# LT3752-Main.net
KiCad netlist of a schematic drawn in Altium Designer
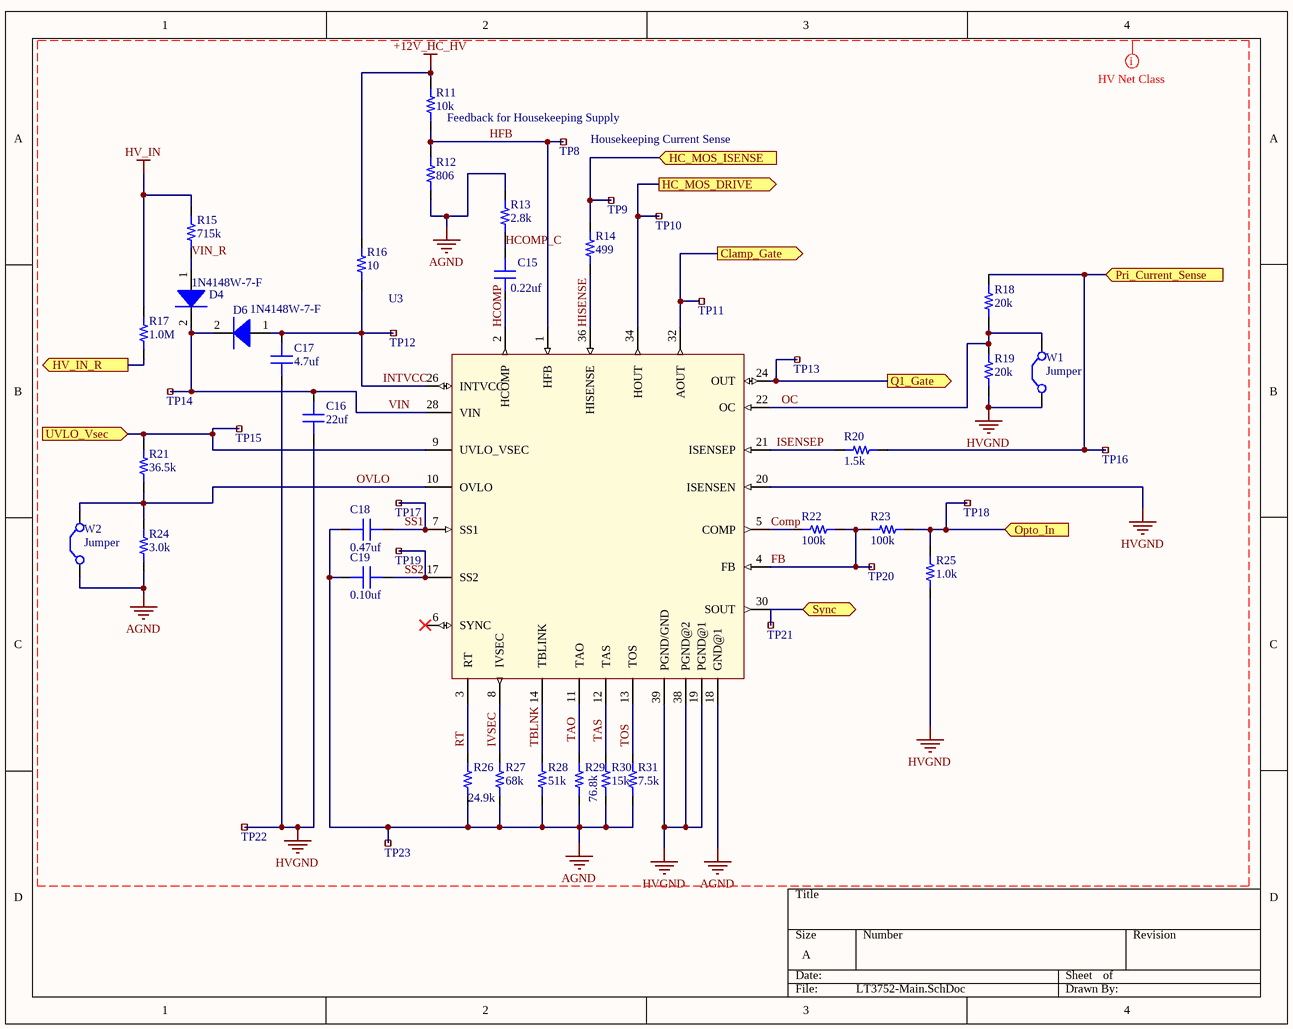
[diagram p0: LT3752-Main.SchDoc]

(export (version "E")
  (design (tool "Eeschema 10.0.6"))
  (components
    (comp (ref "C15")
      (value "0.22uf")
      (footprint "CAP 0603/1608")
      (fields
        (field (name "Comment") "Capacitor MLCC 0.22uf 25V CAP 0603/1608")
        (field (name "CREATED_BY") "Nick Mah")
      )
      (libsource (lib "Altium-Lib") (part "Capacitor"))
    )
    (comp (ref "C16")
      (value "22uf")
      (footprint "CAP 0805/2012")
      (fields
        (field (name "Comment") "Capacitor MLCC 22uf 25V CAP 0805/2012")
        (field (name "CREATED_BY") "Nick Mah")
      )
      (libsource (lib "Altium-Lib") (part "Capacitor"))
    )
    (comp (ref "C17")
      (value "4.7uf")
      (footprint "CAP 0805/2012")
      (fields
        (field (name "Comment") "Capacitor MLCC 4.7uf 25V CAP 0805/2012")
        (field (name "CREATED_BY") "Nick Mah")
      )
      (libsource (lib "Altium-Lib") (part "Capacitor"))
    )
    (comp (ref "C18")
      (value "0.47uf")
      (footprint "CAP 0603/1608")
      (fields
        (field (name "Comment") "Capacitor MLCC 0.47uf 25V CAP 0603/1608")
        (field (name "CREATED_BY") "Nick Mah")
      )
      (libsource (lib "Altium-Lib") (part "Capacitor"))
    )
    (comp (ref "C19")
      (value "0.10uf")
      (footprint "CAP 0603/1608")
      (fields
        (field (name "Comment") "Capacitor MLCC 0.10uf 25V CAP 0603/1608")
        (field (name "CREATED_BY") "Nick Mah")
      )
      (libsource (lib "Altium-Lib") (part "Capacitor"))
    )
    (comp (ref "D4")
      (value "~")
      (footprint "SOD123F")
      (description "100V Reverse DC Voltage")
      (fields (field (name "MFRPARTNO") "1N4148W-7-F"))
      (libsource (lib "Altium-Lib") (part "DIODE"))
    )
    (comp (ref "D6")
      (value "~")
      (footprint "SOD123F")
      (description "100V Reverse DC Voltage")
      (fields (field (name "MFRPARTNO") "1N4148W-7-F"))
      (libsource (lib "Altium-Lib") (part "DIODE"))
    )
    (comp (ref "R11")
      (value "10k")
      (footprint "RES 0603/1608")
      (fields
        (field (name "TOLERANCE") "1%")
        (field (name "POWER") "1/10W")
        (field (name "Comment") "Resistor 10k 0603 1/10W 1%")
        (field (name "CREATED_BY") "Nick Mah")
      )
      (libsource (lib "Altium-Lib") (part "Resistor"))
    )
    (comp (ref "R12")
      (value "806")
      (footprint "RES 0603/1608")
      (fields
        (field (name "TOLERANCE") "1%")
        (field (name "POWER") "1/10W")
        (field (name "Comment") "Resistor 806 0603 1/10W 1%")
        (field (name "CREATED_BY") "Nick Mah")
      )
      (libsource (lib "Altium-Lib") (part "Resistor"))
    )
    (comp (ref "R13")
      (value "2.8k")
      (footprint "RES 0603/1608")
      (fields
        (field (name "TOLERANCE") "1%")
        (field (name "POWER") "1/10W")
        (field (name "Comment") "Resistor 2.8k 0603 1/10W 1%")
        (field (name "CREATED_BY") "Nick Mah")
      )
      (libsource (lib "Altium-Lib") (part "Resistor"))
    )
    (comp (ref "R14")
      (value "499")
      (footprint "RES 0603/1608")
      (fields
        (field (name "TOLERANCE") "1%")
        (field (name "POWER") "1/10W")
        (field (name "Comment") "Resistor 499 0603 1/10W 1%")
        (field (name "CREATED_BY") "Nick Mah")
      )
      (libsource (lib "Altium-Lib") (part "Resistor"))
    )
    (comp (ref "R15")
      (value "715k")
      (footprint "RES 1206/3216")
      (fields
        (field (name "TOLERANCE") "1%")
        (field (name "POWER") "1/4W")
        (field (name "Comment") "Resistor 715k 1206 1/4W 1%")
        (field (name "CREATED_BY") "Nick Mah")
      )
      (libsource (lib "Altium-Lib") (part "Resistor"))
    )
    (comp (ref "R16")
      (value "10")
      (footprint "RES 0805/2012")
      (fields
        (field (name "TOLERANCE") "10%")
        (field (name "POWER") "1/4W")
        (field (name "Comment") "Resistor 10 0805 1/4W 10%")
        (field (name "CREATED_BY") "Nick Mah")
      )
      (libsource (lib "Altium-Lib") (part "Resistor"))
    )
    (comp (ref "R17")
      (value "1.0M")
      (footprint "RES 0603/1608")
      (fields
        (field (name "TOLERANCE") "1%")
        (field (name "POWER") "1/10W")
        (field (name "Comment") "Resistor 1.0M 0603 1/10W 1%")
        (field (name "CREATED_BY") "Nick Mah")
      )
      (libsource (lib "Altium-Lib") (part "Resistor"))
    )
    (comp (ref "R18")
      (value "20k")
      (footprint "RES 0603/1608")
      (fields
        (field (name "TOLERANCE") "1%")
        (field (name "POWER") "1/10W")
        (field (name "Comment") "Resistor 20k 0603 1/10W 1%")
        (field (name "CREATED_BY") "Nick Mah")
      )
      (libsource (lib "Altium-Lib") (part "Resistor"))
    )
    (comp (ref "R19")
      (value "20k")
      (footprint "RES 0603/1608")
      (fields
        (field (name "TOLERANCE") "1%")
        (field (name "POWER") "1/10W")
        (field (name "Comment") "Resistor 20k 0603 1/10W 1%")
        (field (name "CREATED_BY") "Nick Mah")
      )
      (libsource (lib "Altium-Lib") (part "Resistor"))
    )
    (comp (ref "R20")
      (value "1.5k")
      (footprint "RES 0603/1608")
      (fields
        (field (name "TOLERANCE") "1%")
        (field (name "POWER") "1/10W")
        (field (name "Comment") "Resistor 1.5k 0603 1/10W 1%")
        (field (name "CREATED_BY") "Nick Mah")
      )
      (libsource (lib "Altium-Lib") (part "Resistor"))
    )
    (comp (ref "R21")
      (value "36.5k")
      (footprint "RES 0603/1608")
      (fields
        (field (name "TOLERANCE") "1%")
        (field (name "POWER") "1/10W")
        (field (name "Comment") "Resistor 36.5k 0603 1/10W 1%")
        (field (name "CREATED_BY") "Nick Mah")
      )
      (libsource (lib "Altium-Lib") (part "Resistor"))
    )
    (comp (ref "R22")
      (value "100k")
      (footprint "RES 0603/1608")
      (fields
        (field (name "TOLERANCE") "1%")
        (field (name "POWER") "1/10W")
        (field (name "Comment") "Resistor 100k 0603 1/10W 1%")
        (field (name "CREATED_BY") "Nick Mah")
      )
      (libsource (lib "Altium-Lib") (part "Resistor"))
    )
    (comp (ref "R23")
      (value "100k")
      (footprint "RES 0603/1608")
      (fields
        (field (name "TOLERANCE") "1%")
        (field (name "POWER") "1/10W")
        (field (name "Comment") "Resistor 100k 0603 1/10W 1%")
        (field (name "CREATED_BY") "Nick Mah")
      )
      (libsource (lib "Altium-Lib") (part "Resistor"))
    )
    (comp (ref "R24")
      (value "3.0k")
      (footprint "RES 0603/1608")
      (fields
        (field (name "TOLERANCE") "1%")
        (field (name "POWER") "1/10W")
        (field (name "Comment") "Resistor 3.0k 0603 1/10W 1%")
        (field (name "CREATED_BY") "Nick Mah")
      )
      (libsource (lib "Altium-Lib") (part "Resistor"))
    )
    (comp (ref "R25")
      (value "1.0k")
      (footprint "RES 0805/2012")
      (fields
        (field (name "TOLERANCE") "5%")
        (field (name "POWER") "1/4W")
        (field (name "Comment") "Resistor 1.0k 0805 1/4W 5%")
        (field (name "CREATED_BY") "Nick Mah")
      )
      (libsource (lib "Altium-Lib") (part "Resistor"))
    )
    (comp (ref "R26")
      (value "24.9k")
      (footprint "RES 0603/1608")
      (fields
        (field (name "TOLERANCE") "1%")
        (field (name "POWER") "1/10W")
        (field (name "Comment") "Resistor 24.9k 0603 1/10W 1%")
        (field (name "CREATED_BY") "Nick Mah")
      )
      (libsource (lib "Altium-Lib") (part "Resistor"))
    )
    (comp (ref "R27")
      (value "68k")
      (footprint "RES 0603/1608")
      (fields
        (field (name "TOLERANCE") "1%")
        (field (name "POWER") "1/10W")
        (field (name "Comment") "Resistor 68k 0603 1/10W 1%")
        (field (name "CREATED_BY") "Nick Mah")
      )
      (libsource (lib "Altium-Lib") (part "Resistor"))
    )
    (comp (ref "R28")
      (value "51k")
      (footprint "RES 0603/1608")
      (fields
        (field (name "TOLERANCE") "1%")
        (field (name "POWER") "1/10W")
        (field (name "Comment") "Resistor 51k 0603 1/10W 1%")
        (field (name "CREATED_BY") "Nick Mah")
      )
      (libsource (lib "Altium-Lib") (part "Resistor"))
    )
    (comp (ref "R29")
      (value "76.8k")
      (footprint "RES 0603/1608")
      (fields
        (field (name "TOLERANCE") "1%")
        (field (name "POWER") "1/10W")
        (field (name "Comment") "Resistor 76.8k 0603 1/10 1%")
        (field (name "CREATED_BY") "Nick Mah")
      )
      (libsource (lib "Altium-Lib") (part "Resistor"))
    )
    (comp (ref "R30")
      (value "15k")
      (footprint "RES 0603/1608")
      (fields
        (field (name "TOLERANCE") "1%")
        (field (name "POWER") "1/10W")
        (field (name "Comment") "Resistor 15k 0603 1/10W 1%")
        (field (name "CREATED_BY") "Nick Mah")
      )
      (libsource (lib "Altium-Lib") (part "Resistor"))
    )
    (comp (ref "R31")
      (value "7.5k")
      (footprint "RES 0603/1608")
      (fields
        (field (name "TOLERANCE") "1%")
        (field (name "POWER") "1/10W")
        (field (name "Comment") "Resistor 7.5k 0603 1/10W 1%")
        (field (name "CREATED_BY") "Nick Mah")
      )
      (libsource (lib "Altium-Lib") (part "Resistor"))
    )
    (comp (ref "TP8")
      (value "RCU-0C")
      (footprint "5029")
      (description "Test point")
      (fields
        (field (name "MFRPARTNO") "5029")
        (field (name "COMPONENTLINK1URL") "file:///C:/Users/Jason%20Zhou/Downloads/5029.PDF")
        (field (name "CREATED_BY") "Jason Zhou")
      )
      (libsource (lib "Altium-Lib") (part "RCU-0C"))
    )
    (comp (ref "TP9")
      (value "RCU-0C")
      (footprint "5029")
      (description "Test point")
      (fields
        (field (name "MFRPARTNO") "5029")
        (field (name "COMPONENTLINK1URL") "file:///C:/Users/Jason%20Zhou/Downloads/5029.PDF")
        (field (name "CREATED_BY") "Jason Zhou")
      )
      (libsource (lib "Altium-Lib") (part "RCU-0C"))
    )
    (comp (ref "TP10")
      (value "RCU-0C")
      (footprint "5029")
      (description "Test point")
      (fields
        (field (name "MFRPARTNO") "5029")
        (field (name "COMPONENTLINK1URL") "file:///C:/Users/Jason%20Zhou/Downloads/5029.PDF")
        (field (name "CREATED_BY") "Jason Zhou")
      )
      (libsource (lib "Altium-Lib") (part "RCU-0C"))
    )
    (comp (ref "TP11")
      (value "RCU-0C")
      (footprint "5029")
      (description "Test point")
      (fields
        (field (name "MFRPARTNO") "5029")
        (field (name "COMPONENTLINK1URL") "file:///C:/Users/Jason%20Zhou/Downloads/5029.PDF")
        (field (name "CREATED_BY") "Jason Zhou")
      )
      (libsource (lib "Altium-Lib") (part "RCU-0C"))
    )
    (comp (ref "TP12")
      (value "RCU-0C")
      (footprint "5029")
      (description "Test point")
      (fields
        (field (name "MFRPARTNO") "5029")
        (field (name "COMPONENTLINK1URL") "file:///C:/Users/Jason%20Zhou/Downloads/5029.PDF")
        (field (name "CREATED_BY") "Jason Zhou")
      )
      (libsource (lib "Altium-Lib") (part "RCU-0C"))
    )
    (comp (ref "TP13")
      (value "RCU-0C")
      (footprint "5029")
      (description "Test point")
      (fields
        (field (name "MFRPARTNO") "5029")
        (field (name "COMPONENTLINK1URL") "file:///C:/Users/Jason%20Zhou/Downloads/5029.PDF")
        (field (name "CREATED_BY") "Jason Zhou")
      )
      (libsource (lib "Altium-Lib") (part "RCU-0C"))
    )
    (comp (ref "TP14")
      (value "RCU-0C")
      (footprint "5029")
      (description "Test point")
      (fields
        (field (name "MFRPARTNO") "5029")
        (field (name "COMPONENTLINK1URL") "file:///C:/Users/Jason%20Zhou/Downloads/5029.PDF")
        (field (name "CREATED_BY") "Jason Zhou")
      )
      (libsource (lib "Altium-Lib") (part "RCU-0C"))
    )
    (comp (ref "TP15")
      (value "RCU-0C")
      (footprint "5029")
      (description "Test point")
      (fields
        (field (name "MFRPARTNO") "5029")
        (field (name "COMPONENTLINK1URL") "file:///C:/Users/Jason%20Zhou/Downloads/5029.PDF")
        (field (name "CREATED_BY") "Jason Zhou")
      )
      (libsource (lib "Altium-Lib") (part "RCU-0C"))
    )
    (comp (ref "TP16")
      (value "RCU-0C")
      (footprint "5029")
      (description "Test point")
      (fields
        (field (name "MFRPARTNO") "5029")
        (field (name "COMPONENTLINK1URL") "file:///C:/Users/Jason%20Zhou/Downloads/5029.PDF")
        (field (name "CREATED_BY") "Jason Zhou")
      )
      (libsource (lib "Altium-Lib") (part "RCU-0C"))
    )
    (comp (ref "TP17")
      (value "RCU-0C")
      (footprint "5029")
      (description "Test point")
      (fields
        (field (name "MFRPARTNO") "5029")
        (field (name "COMPONENTLINK1URL") "file:///C:/Users/Jason%20Zhou/Downloads/5029.PDF")
        (field (name "CREATED_BY") "Jason Zhou")
      )
      (libsource (lib "Altium-Lib") (part "RCU-0C"))
    )
    (comp (ref "TP18")
      (value "RCU-0C")
      (footprint "5029")
      (description "Test point")
      (fields
        (field (name "MFRPARTNO") "5029")
        (field (name "COMPONENTLINK1URL") "file:///C:/Users/Jason%20Zhou/Downloads/5029.PDF")
        (field (name "CREATED_BY") "Jason Zhou")
      )
      (libsource (lib "Altium-Lib") (part "RCU-0C"))
    )
    (comp (ref "TP19")
      (value "RCU-0C")
      (footprint "5029")
      (description "Test point")
      (fields
        (field (name "MFRPARTNO") "5029")
        (field (name "COMPONENTLINK1URL") "file:///C:/Users/Jason%20Zhou/Downloads/5029.PDF")
        (field (name "CREATED_BY") "Jason Zhou")
      )
      (libsource (lib "Altium-Lib") (part "RCU-0C"))
    )
    (comp (ref "TP20")
      (value "RCU-0C")
      (footprint "5029")
      (description "Test point")
      (fields
        (field (name "MFRPARTNO") "5029")
        (field (name "COMPONENTLINK1URL") "file:///C:/Users/Jason%20Zhou/Downloads/5029.PDF")
        (field (name "CREATED_BY") "Jason Zhou")
      )
      (libsource (lib "Altium-Lib") (part "RCU-0C"))
    )
    (comp (ref "TP21")
      (value "RCU-0C")
      (footprint "5029")
      (description "Test point")
      (fields
        (field (name "MFRPARTNO") "5029")
        (field (name "COMPONENTLINK1URL") "file:///C:/Users/Jason%20Zhou/Downloads/5029.PDF")
        (field (name "CREATED_BY") "Jason Zhou")
      )
      (libsource (lib "Altium-Lib") (part "RCU-0C"))
    )
    (comp (ref "TP22")
      (value "RCU-0C")
      (footprint "5029")
      (description "Test point")
      (fields
        (field (name "MFRPARTNO") "5029")
        (field (name "COMPONENTLINK1URL") "file:///C:/Users/Jason%20Zhou/Downloads/5029.PDF")
        (field (name "CREATED_BY") "Jason Zhou")
      )
      (libsource (lib "Altium-Lib") (part "RCU-0C"))
    )
    (comp (ref "TP23")
      (value "RCU-0C")
      (footprint "5029")
      (description "Test point")
      (fields
        (field (name "MFRPARTNO") "5029")
        (field (name "COMPONENTLINK1URL") "file:///C:/Users/Jason%20Zhou/Downloads/5029.PDF")
        (field (name "CREATED_BY") "Jason Zhou")
      )
      (libsource (lib "Altium-Lib") (part "RCU-0C"))
    )
    (comp (ref "U3")
      (value "~")
      (footprint "TSSOP-38")
      (fields
        (field (name "MF") "Linear Technology/Analog")
        (field (name "MP") "LT3752EFE-1#PBF")
        (field (name "POWER") "400W")
        (field (name "CREATED_BY") "Jason")
      )
      (libsource (lib "Altium-Lib") (part "LT3752-1"))
    )
    (comp (ref "W1")
      (value "Jumper")
      (footprint "XG8T-0231")
      (description "Jumper headers")
      (fields (field (name "MFRPARTNO") "XG8T-0231"))
      (libsource (lib "Altium-Lib") (part "Jumper"))
    )
    (comp (ref "W2")
      (value "Jumper")
      (footprint "XG8T-0231")
      (description "Jumper headers")
      (fields (field (name "MFRPARTNO") "XG8T-0231"))
      (libsource (lib "Altium-Lib") (part "Jumper"))
    )
  )
  (nets
    (net (code "1") (name "+12V_HC_HV") (class "Default")
      (node (ref "R11") (pin "1") (pinfunction "1_1") (pintype "passive"))
      (node (ref "R16") (pin "1") (pinfunction "1_1") (pintype "passive"))
    )
    (net (code "2") (name "/Clamp_Gate") (class "Default")
      (node (ref "TP11") (pin "1") (pintype "passive"))
      (node (ref "U3") (pin "32") (pinfunction "AOUT_32") (pintype "output"))
    )
    (net (code "3") (name "/Comp") (class "Default")
      (node (ref "R22") (pin "1") (pinfunction "1_1") (pintype "passive"))
      (node (ref "U3") (pin "5") (pinfunction "COMP_5") (pintype "output"))
    )
    (net (code "4") (name "/FB") (class "Default")
      (node (ref "R22") (pin "2") (pinfunction "2_2") (pintype "passive"))
      (node (ref "R23") (pin "1") (pinfunction "1_1") (pintype "passive"))
      (node (ref "TP20") (pin "1") (pintype "passive"))
      (node (ref "U3") (pin "4") (pinfunction "FB_4") (pintype "input"))
    )
    (net (code "5") (name "/HCOMP") (class "Default")
      (node (ref "C15") (pin "1") (pinfunction "1_1") (pintype "passive"))
      (node (ref "U3") (pin "2") (pinfunction "HCOMP_2") (pintype "output"))
    )
    (net (code "6") (name "/HCOMP_C") (class "Default")
      (node (ref "C15") (pin "2") (pinfunction "2_2") (pintype "passive"))
      (node (ref "R13") (pin "1") (pinfunction "1_1") (pintype "passive"))
    )
    (net (code "7") (name "/HC_MOS_DRIVE") (class "Default")
      (node (ref "TP10") (pin "1") (pintype "passive"))
      (node (ref "U3") (pin "34") (pinfunction "HOUT_34") (pintype "output"))
    )
    (net (code "8") (name "/HC_MOS_ISENSE") (class "Default")
      (node (ref "R14") (pin "2") (pinfunction "2_2") (pintype "passive"))
      (node (ref "TP9") (pin "1") (pintype "passive"))
    )
    (net (code "9") (name "/HFB") (class "Default")
      (node (ref "R11") (pin "2") (pinfunction "2_2") (pintype "passive"))
      (node (ref "R12") (pin "2") (pinfunction "2_2") (pintype "passive"))
      (node (ref "TP8") (pin "1") (pintype "passive"))
      (node (ref "U3") (pin "1") (pinfunction "HFB_1") (pintype "input"))
    )
    (net (code "10") (name "/HISENSE") (class "Default")
      (node (ref "R14") (pin "1") (pinfunction "1_1") (pintype "passive"))
      (node (ref "U3") (pin "36") (pinfunction "HISENSE_36") (pintype "input"))
    )
    (net (code "11") (name "/HV_IN_R") (class "Default")
      (node (ref "R17") (pin "2") (pinfunction "2_2") (pintype "passive"))
    )
    (net (code "12") (name "/INTVCC") (class "Default")
      (node (ref "C17") (pin "2") (pinfunction "2_2") (pintype "passive"))
      (node (ref "D6") (pin "1") (pinfunction "A_1") (pintype "passive"))
      (node (ref "R16") (pin "2") (pinfunction "2_2") (pintype "passive"))
      (node (ref "TP12") (pin "1") (pintype "passive"))
      (node (ref "U3") (pin "26") (pinfunction "INTVCC_26") (pintype "bidirectional"))
    )
    (net (code "13") (name "/ISENSEP") (class "Default")
      (node (ref "R20") (pin "1") (pinfunction "1_1") (pintype "passive"))
      (node (ref "U3") (pin "21") (pinfunction "ISENSEP_21") (pintype "input"))
    )
    (net (code "14") (name "/IVSEC") (class "Default")
      (node (ref "R27") (pin "2") (pinfunction "2_2") (pintype "passive"))
      (node (ref "U3") (pin "8") (pinfunction "IVSEC_8") (pintype "output"))
    )
    (net (code "15") (name "/OC") (class "Default")
      (node (ref "R18") (pin "1") (pinfunction "1_1") (pintype "passive"))
      (node (ref "R19") (pin "2") (pinfunction "2_2") (pintype "passive"))
      (node (ref "U3") (pin "22") (pinfunction "OC_22") (pintype "input"))
      (node (ref "W1") (pin "2") (pinfunction "C2_2") (pintype "passive"))
    )
    (net (code "16") (name "/OVLO") (class "Default")
      (node (ref "R21") (pin "1") (pinfunction "1_1") (pintype "passive"))
      (node (ref "R24") (pin "2") (pinfunction "2_2") (pintype "passive"))
      (node (ref "U3") (pin "10") (pinfunction "OVLO_10") (pintype "passive"))
      (node (ref "W2") (pin "2") (pinfunction "C2_2") (pintype "passive"))
    )
    (net (code "17") (name "/Opto_In") (class "Default")
      (node (ref "R23") (pin "2") (pinfunction "2_2") (pintype "passive"))
      (node (ref "R25") (pin "2") (pinfunction "2_2") (pintype "passive"))
      (node (ref "TP18") (pin "1") (pintype "passive"))
    )
    (net (code "18") (name "/Pri_Current_Sense") (class "Default")
      (node (ref "R18") (pin "2") (pinfunction "2_2") (pintype "passive"))
      (node (ref "R20") (pin "2") (pinfunction "2_2") (pintype "passive"))
      (node (ref "TP16") (pin "1") (pintype "passive"))
    )
    (net (code "19") (name "/Q1_Gate") (class "Default")
      (node (ref "TP13") (pin "1") (pintype "passive"))
      (node (ref "U3") (pin "24") (pinfunction "OUT_24") (pintype "bidirectional"))
    )
    (net (code "20") (name "/RT") (class "Default")
      (node (ref "R26") (pin "2") (pinfunction "2_2") (pintype "passive"))
      (node (ref "U3") (pin "3") (pinfunction "RT_3") (pintype "passive"))
    )
    (net (code "21") (name "/SS1") (class "Default")
      (node (ref "C18") (pin "2") (pinfunction "2_2") (pintype "passive"))
      (node (ref "TP17") (pin "1") (pintype "passive"))
      (node (ref "U3") (pin "7") (pinfunction "SS1_7") (pintype "input"))
    )
    (net (code "22") (name "/SS2") (class "Default")
      (node (ref "C19") (pin "2") (pinfunction "2_2") (pintype "passive"))
      (node (ref "TP19") (pin "1") (pintype "passive"))
      (node (ref "U3") (pin "17") (pinfunction "SS2_17") (pintype "passive"))
    )
    (net (code "23") (name "/Sync") (class "Default")
      (node (ref "TP21") (pin "1") (pintype "passive"))
      (node (ref "U3") (pin "30") (pinfunction "SOUT_30") (pintype "output"))
    )
    (net (code "24") (name "/TAO") (class "Default")
      (node (ref "R29") (pin "2") (pinfunction "2_2") (pintype "passive"))
      (node (ref "U3") (pin "11") (pinfunction "TAO_11") (pintype "passive"))
    )
    (net (code "25") (name "/TAS") (class "Default")
      (node (ref "R30") (pin "2") (pinfunction "2_2") (pintype "passive"))
      (node (ref "U3") (pin "12") (pinfunction "TAS_12") (pintype "passive"))
    )
    (net (code "26") (name "/TBLNK") (class "Default")
      (node (ref "R28") (pin "2") (pinfunction "2_2") (pintype "passive"))
      (node (ref "U3") (pin "14") (pinfunction "TBLINK_14") (pintype "passive"))
    )
    (net (code "27") (name "/TOS") (class "Default")
      (node (ref "R31") (pin "2") (pinfunction "2_2") (pintype "passive"))
      (node (ref "U3") (pin "13") (pinfunction "TOS_13") (pintype "passive"))
    )
    (net (code "28") (name "/UVLO_Vsec") (class "Default")
      (node (ref "R21") (pin "2") (pinfunction "2_2") (pintype "passive"))
      (node (ref "TP15") (pin "1") (pintype "passive"))
      (node (ref "U3") (pin "9") (pinfunction "UVLO_VSEC_9") (pintype "passive"))
    )
    (net (code "29") (name "/VIN") (class "Default")
      (node (ref "C16") (pin "2") (pinfunction "2_2") (pintype "passive"))
      (node (ref "D4") (pin "2") (pinfunction "K_2") (pintype "passive"))
      (node (ref "D6") (pin "2") (pinfunction "K_2") (pintype "passive"))
      (node (ref "TP14") (pin "1") (pintype "passive"))
      (node (ref "U3") (pin "28") (pinfunction "VIN_28") (pintype "power_in"))
    )
    (net (code "30") (name "/VIN_R") (class "Default")
      (node (ref "D4") (pin "1") (pinfunction "A_1") (pintype "passive"))
      (node (ref "R15") (pin "1") (pinfunction "1_1") (pintype "passive"))
    )
    (net (code "31") (name "AGND") (class "Default")
      (node (ref "C18") (pin "1") (pinfunction "1_1") (pintype "passive"))
      (node (ref "C19") (pin "1") (pinfunction "1_1") (pintype "passive"))
      (node (ref "R12") (pin "1") (pinfunction "1_1") (pintype "passive"))
      (node (ref "R13") (pin "2") (pinfunction "2_2") (pintype "passive"))
      (node (ref "R24") (pin "1") (pinfunction "1_1") (pintype "passive"))
      (node (ref "R26") (pin "1") (pinfunction "1_1") (pintype "passive"))
      (node (ref "R27") (pin "1") (pinfunction "1_1") (pintype "passive"))
      (node (ref "R28") (pin "1") (pinfunction "1_1") (pintype "passive"))
      (node (ref "R29") (pin "1") (pinfunction "1_1") (pintype "passive"))
      (node (ref "R30") (pin "1") (pinfunction "1_1") (pintype "passive"))
      (node (ref "R31") (pin "1") (pinfunction "1_1") (pintype "passive"))
      (node (ref "TP23") (pin "1") (pintype "passive"))
      (node (ref "U3") (pin "18") (pinfunction "GND@1_18") (pintype "power_in"))
      (node (ref "W2") (pin "1") (pinfunction "C1_1") (pintype "passive"))
    )
    (net (code "32") (name "HVGND") (class "Default")
      (node (ref "C16") (pin "1") (pinfunction "1_1") (pintype "passive"))
      (node (ref "C17") (pin "1") (pinfunction "1_1") (pintype "passive"))
      (node (ref "R19") (pin "1") (pinfunction "1_1") (pintype "passive"))
      (node (ref "R25") (pin "1") (pinfunction "1_1") (pintype "passive"))
      (node (ref "TP22") (pin "1") (pintype "passive"))
      (node (ref "U3") (pin "19") (pinfunction "PGND@1_19") (pintype "power_in"))
      (node (ref "U3") (pin "20") (pinfunction "ISENSEN_20") (pintype "input"))
      (node (ref "U3") (pin "38") (pinfunction "PGND@2_38") (pintype "power_in"))
      (node (ref "U3") (pin "39") (pinfunction "PGND/GND_39") (pintype "power_in"))
      (node (ref "W1") (pin "1") (pinfunction "C1_1") (pintype "passive"))
    )
    (net (code "33") (name "HV_IN") (class "Default")
      (node (ref "R15") (pin "2") (pinfunction "2_2") (pintype "passive"))
      (node (ref "R17") (pin "1") (pinfunction "1_1") (pintype "passive"))
    )
    (net (code "34") (name "unconnected-(U3-SYNC-Pad6)") (class "Default")
      (node (ref "U3") (pin "6") (pinfunction "SYNC_6") (pintype "bidirectional+no_connect"))
    )
  )
)
